# geneva-interface.net
KiCad netlist of a schematic drawn in Altium Designer
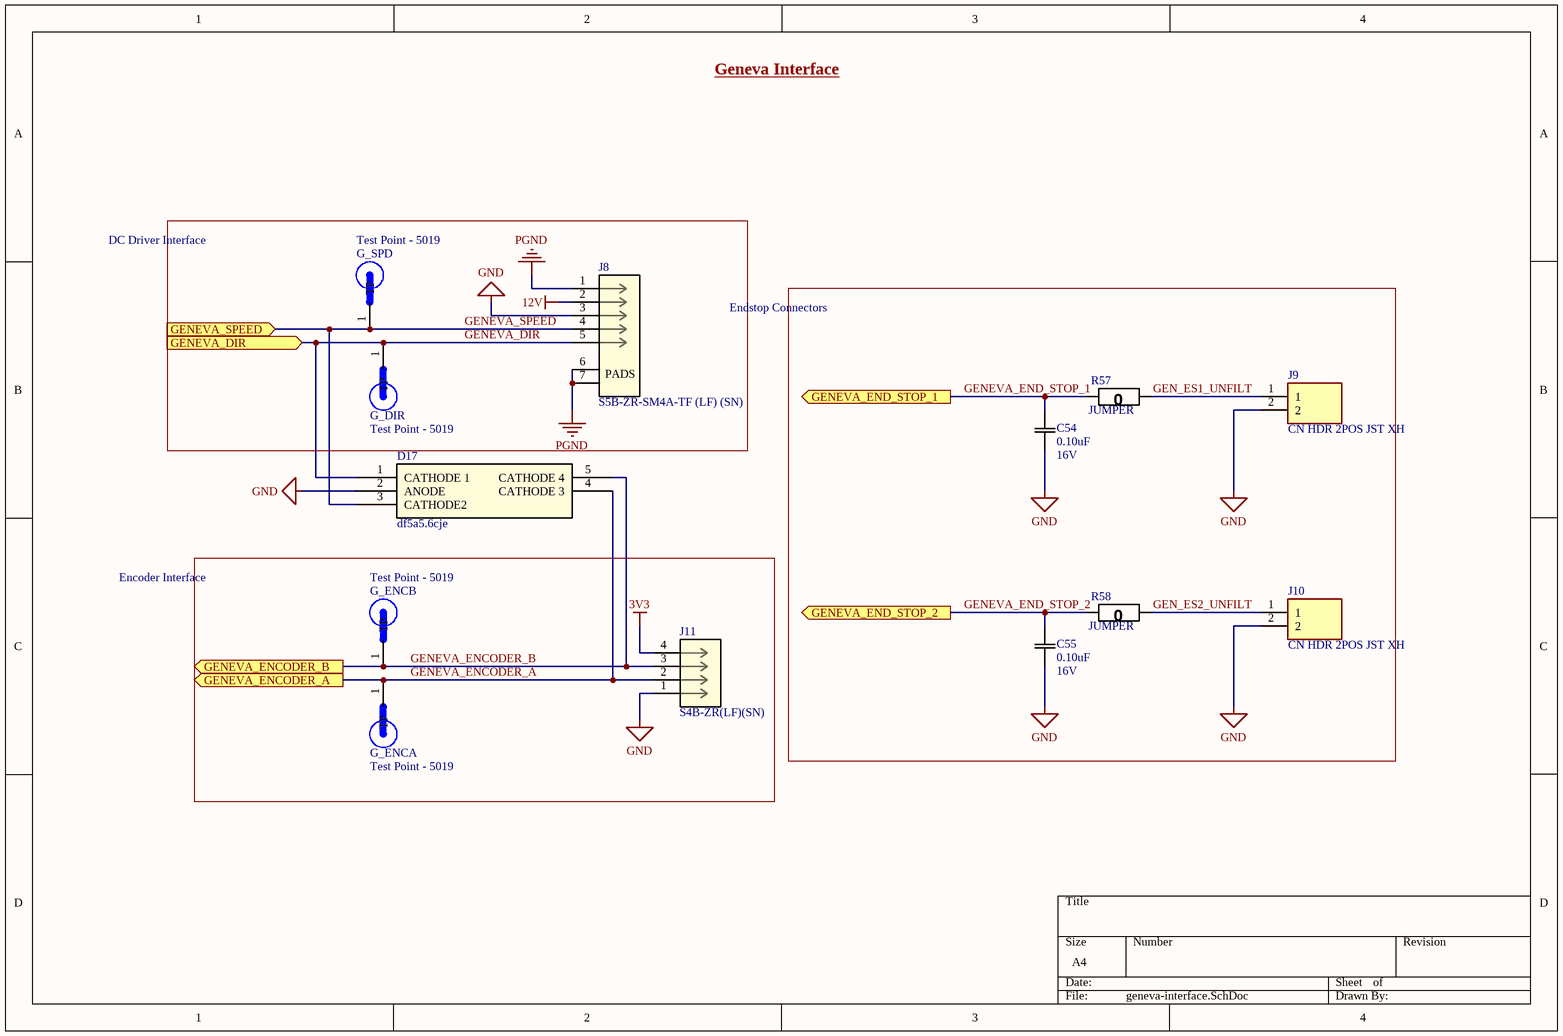
[diagram p0: geneva-interface.SchDoc]

(export (version "E")
  (design (tool "Eeschema 10.0.6"))
  (components
    (comp (ref "C54")
      (value "0.10uF")
      (footprint "0603")
      (description "CAP CER 0.10UF 16V X5R 0603/0805")
      (fields (field (name "TOLERANCE") "10%") (field (name "RATING") "16V"))
      (libsource (lib "AltiumLibraries") (part "CAP 0.10uF 16V"))
    )
    (comp (ref "C55")
      (value "0.10uF")
      (footprint "0603")
      (description "CAP CER 0.10UF 16V X5R 0603/0805")
      (fields (field (name "TOLERANCE") "10%") (field (name "RATING") "16V"))
      (libsource (lib "AltiumLibraries") (part "CAP 0.10uF 16V"))
    )
    (comp (ref "D17")
      (value "df5a5.6cje")
      (footprint "ESV_TOS-L")
      (description "- Clamp - Ipp Tvs Diode Surface Mount ESV 4 Channel")
      (fields
        (field (name "MANUFACTURER_PART_NUMBER") "df5a5.6cje(te85l")
        (field (name "COPYRIGHT") "Copyright (C) 2021 Ultra Librarian. All rights reserved.")
      )
      (libsource (lib "AltiumLibraries") (part "DIODE TVS 3.5 VWM 4 Channel"))
    )
    (comp (ref "G_DIR")
      (value "Test Point - 5019")
      (footprint "TP380X203")
      (description "PC Test Point, Miniature Phosphor Bronze, Silver Plating Surface Mount Mounting Type")
      (fields (field (name "MP") "5019") (field (name "MF") "Keystone Electronics"))
      (libsource (lib "AltiumLibraries") (part "Test Point - 5019"))
    )
    (comp (ref "G_ENCA")
      (value "Test Point - 5019")
      (footprint "TP380X203")
      (description "PC Test Point, Miniature Phosphor Bronze, Silver Plating Surface Mount Mounting Type")
      (fields (field (name "MP") "5019") (field (name "MF") "Keystone Electronics"))
      (libsource (lib "AltiumLibraries") (part "Test Point - 5019"))
    )
    (comp (ref "G_ENCB")
      (value "Test Point - 5019")
      (footprint "TP380X203")
      (description "PC Test Point, Miniature Phosphor Bronze, Silver Plating Surface Mount Mounting Type")
      (fields (field (name "MP") "5019") (field (name "MF") "Keystone Electronics"))
      (libsource (lib "AltiumLibraries") (part "Test Point - 5019"))
    )
    (comp (ref "G_SPD")
      (value "Test Point - 5019")
      (footprint "TP380X203")
      (description "PC Test Point, Miniature Phosphor Bronze, Silver Plating Surface Mount Mounting Type")
      (fields (field (name "MP") "5019") (field (name "MF") "Keystone Electronics"))
      (libsource (lib "AltiumLibraries") (part "Test Point - 5019"))
    )
    (comp (ref "J8")
      (value "S5B-ZR-SM4A-TF (LF) (SN)")
      (footprint "JST_S5B-ZR-SM4A-TF")
      (description "Connector Header Surface Mount, Right Angle 5 position 0.059\" (1.50mm)")
      (fields (field (name "COPYRIGHT") "Copyright (C) 2021 Ultra Librarian. All rights reserved."))
      (libsource (lib "AltiumLibraries") (part "CN 5POS JST ZR RA"))
    )
    (comp (ref "J9")
      (value "CN HDR 2POS JST XH")
      (footprint "JST_B2B-XH-A(LF)(SN)")
      (description "Connector Header Through Hole 2 position 0.098 _2.50mm_\r\nJST XH")
      (fields (field (name "MP") "B2B-XH-A_LF__SN_") (field (name "MF") "JST Sales"))
      (libsource (lib "AltiumLibraries") (part "CN HDR 2POS JST XH"))
    )
    (comp (ref "J10")
      (value "CN HDR 2POS JST XH")
      (footprint "JST_B2B-XH-A(LF)(SN)")
      (description "Connector Header Through Hole 2 position 0.098 _2.50mm_\r\nJST XH")
      (fields (field (name "MP") "B2B-XH-A_LF__SN_") (field (name "MF") "JST Sales"))
      (libsource (lib "AltiumLibraries") (part "CN HDR 2POS JST XH"))
    )
    (comp (ref "J11")
      (value "S4B-ZR(LF)(SN)")
      (footprint "CN S4B-ZR(LF)(SN)_JST")
      (description "Connector Header Through Hole, Right Angle 4 position 0.059\" (1.50mm)")
      (fields (field (name "COPYRIGHT") "Copyright (C) 2021 Ultra Librarian. All rights reserved."))
      (libsource (lib "AltiumLibraries") (part "CN HDR 4POS JST ZR"))
    )
    (comp (ref "R57")
      (value "JUMPER")
      (footprint "0603")
      (description "RES SMD 0 OHM JUMPER GENERIC 0805/0603")
      (libsource (lib "AltiumLibraries") (part "RES 0 JUMPER"))
    )
    (comp (ref "R58")
      (value "JUMPER")
      (footprint "0603")
      (description "RES SMD 0 OHM JUMPER GENERIC 0805/0603")
      (libsource (lib "AltiumLibraries") (part "RES 0 JUMPER"))
    )
  )
  (nets
    (net (code "1") (name "/GENEVA_DIR") (class "Default")
      (node (ref "D17") (pin "1") (pinfunction "CATHODE_1_1") (pintype "passive"))
      (node (ref "G_DIR") (pin "1") (pinfunction "TP_1") (pintype "passive"))
      (node (ref "J8") (pin "5") (pinfunction "5_5") (pintype "passive"))
    )
    (net (code "2") (name "/GENEVA_ENCODER_A") (class "Default")
      (node (ref "D17") (pin "4") (pinfunction "CATHODE_3_4") (pintype "passive"))
      (node (ref "G_ENCA") (pin "1") (pinfunction "TP_1") (pintype "passive"))
      (node (ref "J11") (pin "2") (pinfunction "2_2") (pintype "passive"))
    )
    (net (code "3") (name "/GENEVA_ENCODER_B") (class "Default")
      (node (ref "D17") (pin "5") (pinfunction "CATHODE_4_5") (pintype "passive"))
      (node (ref "G_ENCB") (pin "1") (pinfunction "TP_1") (pintype "passive"))
      (node (ref "J11") (pin "3") (pinfunction "3_3") (pintype "passive"))
    )
    (net (code "4") (name "/GENEVA_END_STOP_1") (class "Default")
      (node (ref "C54") (pin "1") (pinfunction "C1_1") (pintype "passive"))
      (node (ref "R57") (pin "2") (pinfunction "R2_2") (pintype "passive"))
    )
    (net (code "5") (name "/GENEVA_END_STOP_2") (class "Default")
      (node (ref "C55") (pin "1") (pinfunction "C1_1") (pintype "passive"))
      (node (ref "R58") (pin "2") (pinfunction "R2_2") (pintype "passive"))
    )
    (net (code "6") (name "/GENEVA_SPEED") (class "Default")
      (node (ref "D17") (pin "3") (pinfunction "CATHODE2_3") (pintype "passive"))
      (node (ref "G_SPD") (pin "1") (pinfunction "TP_1") (pintype "passive"))
      (node (ref "J8") (pin "4") (pinfunction "4_4") (pintype "passive"))
    )
    (net (code "7") (name "/GEN_ES1_UNFILT") (class "Default")
      (node (ref "J9") (pin "1") (pinfunction "1_1") (pintype "passive"))
      (node (ref "R57") (pin "1") (pinfunction "R1_1") (pintype "passive"))
    )
    (net (code "8") (name "/GEN_ES2_UNFILT") (class "Default")
      (node (ref "J10") (pin "1") (pinfunction "1_1") (pintype "passive"))
      (node (ref "R58") (pin "1") (pinfunction "R1_1") (pintype "passive"))
    )
    (net (code "9") (name "3V3") (class "Default")
      (node (ref "J11") (pin "4") (pinfunction "4_4") (pintype "passive"))
    )
    (net (code "10") (name "12V") (class "Default")
      (node (ref "J8") (pin "2") (pinfunction "2_2") (pintype "passive"))
    )
    (net (code "11") (name "GND") (class "Default")
      (node (ref "C54") (pin "2") (pinfunction "C2_2") (pintype "passive"))
      (node (ref "C55") (pin "2") (pinfunction "C2_2") (pintype "passive"))
      (node (ref "D17") (pin "2") (pinfunction "ANODE_2") (pintype "passive"))
      (node (ref "J10") (pin "2") (pinfunction "2_2") (pintype "passive"))
      (node (ref "J11") (pin "1") (pinfunction "1_1") (pintype "passive"))
      (node (ref "J8") (pin "3") (pinfunction "3_3") (pintype "passive"))
      (node (ref "J9") (pin "2") (pinfunction "2_2") (pintype "passive"))
    )
    (net (code "12") (name "PGND") (class "Default")
      (node (ref "J8") (pin "1") (pinfunction "1_1") (pintype "passive"))
      (node (ref "J8") (pin "6") (pinfunction "6_6") (pintype "passive"))
      (node (ref "J8") (pin "7") (pinfunction "7_7") (pintype "passive"))
    )
  )
)
